# kamstrup-wifi.net
KiCad netlist of a schematic drawn in EAGLE
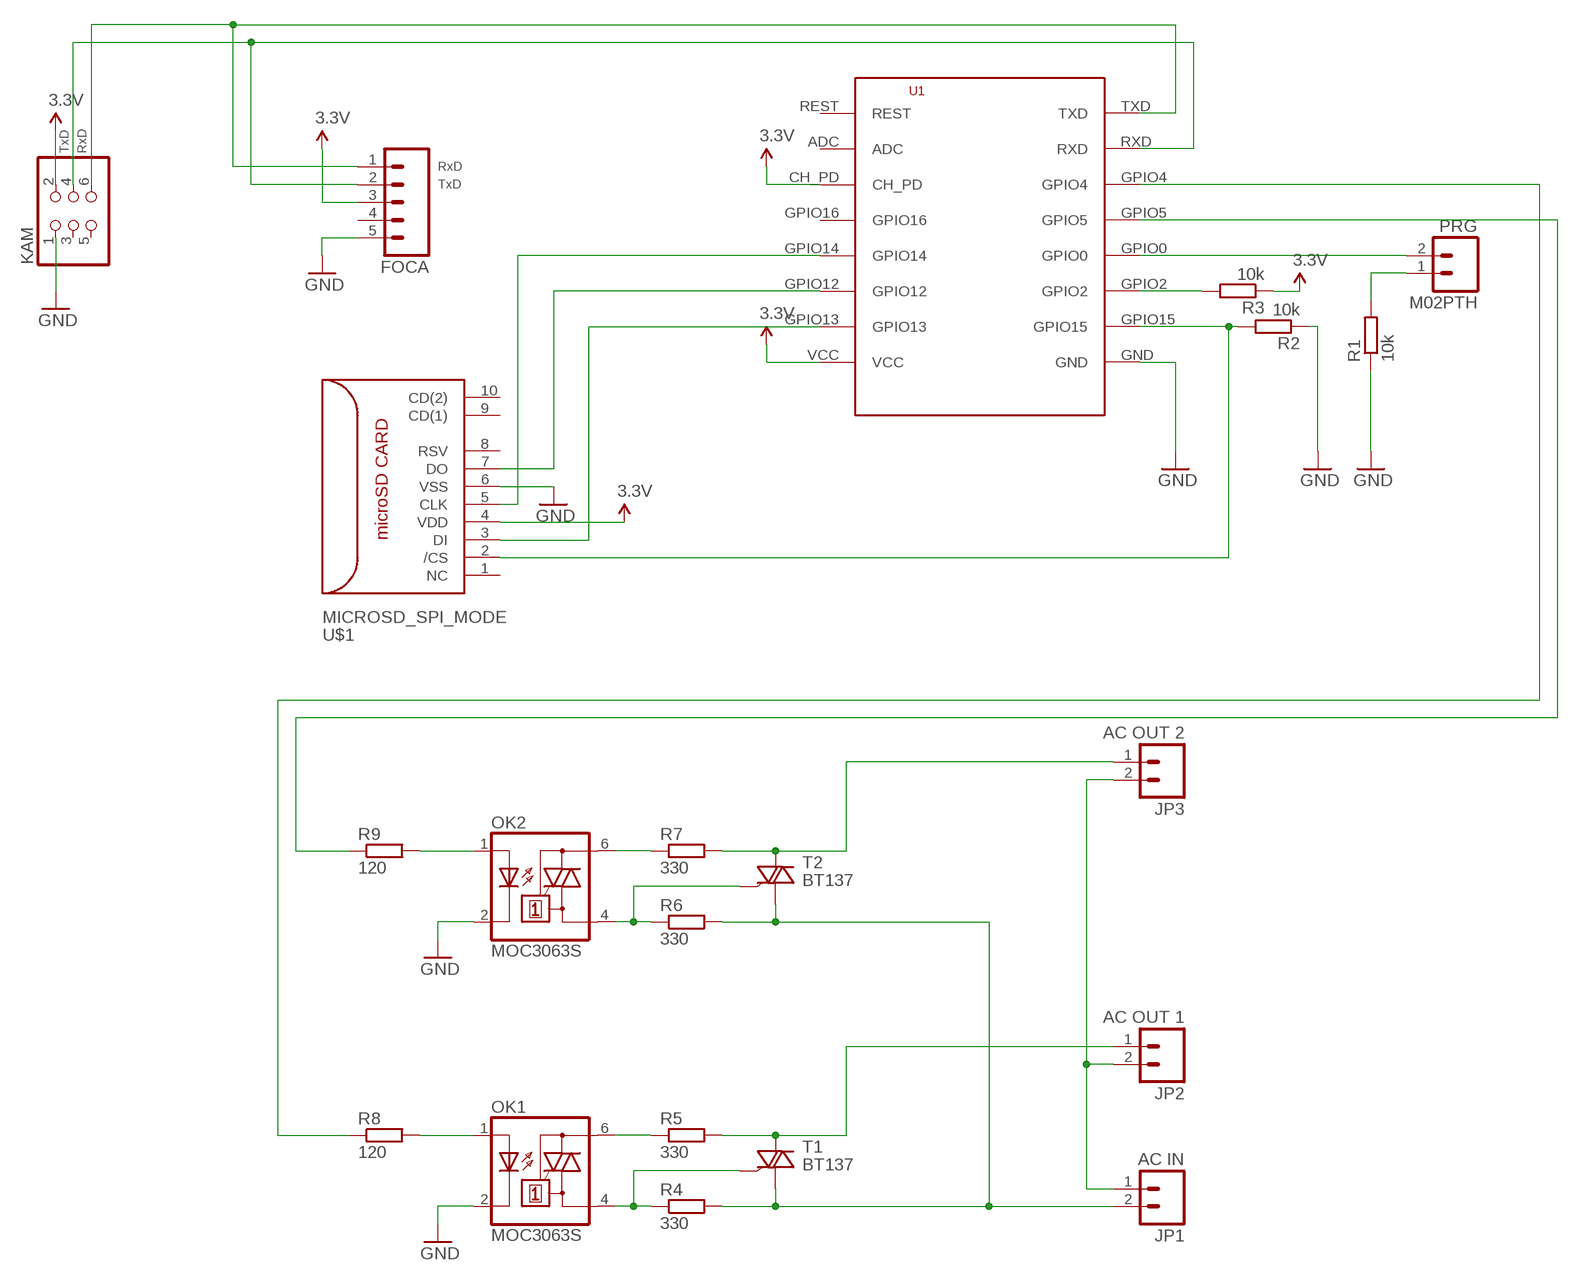
[diagram p0: schematic, sheet 1]

(export (version "E")
  (design (tool "Eeschema 10.0.6"))
  (components
    (comp (ref "FOCA")
      (value "M05PTH")
      (footprint "eagle-import:1X05")
      (libsource (lib "eagle-import") (part "M05PTH"))
    )
    (comp (ref "JP1")
      (value "AC IN")
      (footprint "eagle-import:SCREWTERMINAL-5MM-2")
      (libsource (lib "eagle-import") (part "TE Terminal Block 45 degrees_M025MM"))
    )
    (comp (ref "JP2")
      (value "AC OUT 1")
      (footprint "eagle-import:SCREWTERMINAL-5MM-2")
      (libsource (lib "eagle-import") (part "TE Terminal Block 45 degrees_M025MM"))
    )
    (comp (ref "JP3")
      (value "AC OUT 2")
      (footprint "eagle-import:SCREWTERMINAL-5MM-2")
      (libsource (lib "eagle-import") (part "TE Terminal Block 45 degrees_M025MM"))
    )
    (comp (ref "KAM")
      (value "PINHD-2X3")
      (footprint "eagle-import:2X03")
      (libsource (lib "eagle-import") (part "PINHD-2X3"))
    )
    (comp (ref "OK1")
      (value "MOC3063S")
      (footprint "eagle-import:DIL6-SMD")
      (fields (field (name "MF") "FAIRCHILD SEMICONDUCTOR") (field (name "MPN") "MOC3043SM"))
      (libsource (lib "eagle-import") (part "MOC30S43"))
    )
    (comp (ref "OK2")
      (value "MOC3063S")
      (footprint "eagle-import:DIL6-SMD")
      (fields (field (name "MF") "FAIRCHILD SEMICONDUCTOR") (field (name "MPN") "MOC3043SM"))
      (libsource (lib "eagle-import") (part "MOC30S43"))
    )
    (comp (ref "PRG")
      (value "M02PTH")
      (footprint "eagle-import:1X02")
      (libsource (lib "eagle-import") (part "M02PTH"))
    )
    (comp (ref "R1")
      (value "10k")
      (footprint "eagle-import:R0805")
      (libsource (lib "eagle-import") (part "R-EU_R0805"))
    )
    (comp (ref "R2")
      (value "10k")
      (footprint "eagle-import:R0805")
      (libsource (lib "eagle-import") (part "R-EU_R0805"))
    )
    (comp (ref "R3")
      (value "10k")
      (footprint "eagle-import:R0805")
      (libsource (lib "eagle-import") (part "R-EU_R0805"))
    )
    (comp (ref "R4")
      (value "330")
      (footprint "eagle-import:R0805")
      (libsource (lib "eagle-import") (part "R-EU_R0805"))
    )
    (comp (ref "R5")
      (value "330")
      (footprint "eagle-import:R0805")
      (libsource (lib "eagle-import") (part "R-EU_R0805"))
    )
    (comp (ref "R6")
      (value "330")
      (footprint "eagle-import:R0805")
      (libsource (lib "eagle-import") (part "R-EU_R0805"))
    )
    (comp (ref "R7")
      (value "330")
      (footprint "eagle-import:R0805")
      (libsource (lib "eagle-import") (part "R-EU_R0805"))
    )
    (comp (ref "R8")
      (value "120")
      (footprint "eagle-import:R0805")
      (libsource (lib "eagle-import") (part "R-EU_R0805"))
    )
    (comp (ref "R9")
      (value "120")
      (footprint "eagle-import:R0805")
      (libsource (lib "eagle-import") (part "R-EU_R0805"))
    )
    (comp (ref "T1")
      (value "BT137")
      (footprint "eagle-import:SOT428")
      (libsource (lib "eagle-import") (part "BT137"))
    )
    (comp (ref "T2")
      (value "BT137")
      (footprint "eagle-import:SOT428")
      (libsource (lib "eagle-import") (part "BT137"))
    )
    (comp (ref "U$1")
      (value "MICROSD_SPI_MODE")
      (footprint "eagle-import:MICRO_SD_CONNECTOR")
      (libsource (lib "eagle-import") (part "MICROSD_SPI_MODE"))
    )
    (comp (ref "U1")
      (value "ESP8266-07")
      (footprint "eagle-import:ESP-07")
      (libsource (lib "eagle-import") (part "ESP8266-07"))
    )
  )
  (nets
    (net (code "1") (name "3.3V") (class "Default")
      (node (ref "FOCA") (pin "3") (pinfunction "3_3") (pintype "passive"))
      (node (ref "KAM") (pin "2") (pinfunction "2_2") (pintype "passive"))
      (node (ref "R3") (pin "1") (pinfunction "1_1") (pintype "passive"))
      (node (ref "U$1") (pin "4") (pinfunction "VDD_4") (pintype "bidirectional"))
      (node (ref "U1") (pin "CH_PD") (pinfunction "CH_PD_CH_PD") (pintype "bidirectional"))
      (node (ref "U1") (pin "VCC") (pinfunction "VCC_VCC") (pintype "bidirectional"))
    )
    (net (code "2") (name "GND") (class "Default")
      (node (ref "FOCA") (pin "5") (pinfunction "5_5") (pintype "passive"))
      (node (ref "KAM") (pin "1") (pinfunction "1_1") (pintype "passive"))
      (node (ref "OK1") (pin "2") (pinfunction "C_2") (pintype "passive"))
      (node (ref "OK2") (pin "2") (pinfunction "C_2") (pintype "passive"))
      (node (ref "R1") (pin "1") (pinfunction "1_1") (pintype "passive"))
      (node (ref "R2") (pin "1") (pinfunction "1_1") (pintype "passive"))
      (node (ref "U$1") (pin "6") (pinfunction "VSS_6") (pintype "bidirectional"))
      (node (ref "U1") (pin "GND") (pinfunction "GND_GND") (pintype "power_in"))
    )
    (net (code "3") (name "Net-(FOCA-Pad1)") (class "Default")
      (node (ref "FOCA") (pin "1") (pinfunction "1_1") (pintype "passive"))
      (node (ref "KAM") (pin "6") (pinfunction "6_6") (pintype "passive"))
      (node (ref "U1") (pin "TXD") (pinfunction "TXD_TXD") (pintype "bidirectional"))
    )
    (net (code "4") (name "Net-(FOCA-Pad2)") (class "Default")
      (node (ref "FOCA") (pin "2") (pinfunction "2_2") (pintype "passive"))
      (node (ref "KAM") (pin "4") (pinfunction "4_4") (pintype "passive"))
      (node (ref "U1") (pin "RXD") (pinfunction "RXD_RXD") (pintype "bidirectional"))
    )
    (net (code "5") (name "Net-(JP1-Pad1)") (class "Default")
      (node (ref "JP1") (pin "1") (pinfunction "1_1") (pintype "passive"))
      (node (ref "JP2") (pin "2") (pinfunction "2_2") (pintype "passive"))
      (node (ref "JP3") (pin "2") (pinfunction "2_2") (pintype "passive"))
    )
    (net (code "6") (name "Net-(OK1-A)") (class "Default")
      (node (ref "OK1") (pin "1") (pinfunction "A_1") (pintype "passive"))
      (node (ref "R8") (pin "2") (pinfunction "2_2") (pintype "passive"))
    )
    (net (code "7") (name "Net-(OK1-A1)") (class "Default")
      (node (ref "OK1") (pin "4") (pinfunction "A1_4") (pintype "passive"))
      (node (ref "R4") (pin "1") (pinfunction "1_1") (pintype "passive"))
      (node (ref "T1") (pin "3") (pinfunction "G_3") (pintype "passive"))
    )
    (net (code "8") (name "Net-(OK1-A2)") (class "Default")
      (node (ref "OK1") (pin "6") (pinfunction "A2_6") (pintype "passive"))
      (node (ref "R5") (pin "1") (pinfunction "1_1") (pintype "passive"))
    )
    (net (code "9") (name "Net-(OK2-A)") (class "Default")
      (node (ref "OK2") (pin "1") (pinfunction "A_1") (pintype "passive"))
      (node (ref "R9") (pin "2") (pinfunction "2_2") (pintype "passive"))
    )
    (net (code "10") (name "Net-(OK2-A1)") (class "Default")
      (node (ref "OK2") (pin "4") (pinfunction "A1_4") (pintype "passive"))
      (node (ref "R6") (pin "1") (pinfunction "1_1") (pintype "passive"))
      (node (ref "T2") (pin "3") (pinfunction "G_3") (pintype "passive"))
    )
    (net (code "11") (name "Net-(OK2-A2)") (class "Default")
      (node (ref "OK2") (pin "6") (pinfunction "A2_6") (pintype "passive"))
      (node (ref "R7") (pin "1") (pinfunction "1_1") (pintype "passive"))
    )
    (net (code "12") (name "Net-(PRG-Pad1)") (class "Default")
      (node (ref "PRG") (pin "1") (pinfunction "1_1") (pintype "passive"))
      (node (ref "R1") (pin "2") (pinfunction "2_2") (pintype "passive"))
    )
    (net (code "13") (name "Net-(PRG-Pad2)") (class "Default")
      (node (ref "PRG") (pin "2") (pinfunction "2_2") (pintype "passive"))
      (node (ref "U1") (pin "GPIO0") (pinfunction "GPIO0_GPIO0") (pintype "bidirectional"))
    )
    (net (code "14") (name "Net-(R3-Pad2)") (class "Default")
      (node (ref "R3") (pin "2") (pinfunction "2_2") (pintype "passive"))
      (node (ref "U1") (pin "GPIO2") (pinfunction "GPIO2_GPIO2") (pintype "bidirectional"))
    )
    (net (code "15") (name "Net-(R8-Pad1)") (class "Default")
      (node (ref "R8") (pin "1") (pinfunction "1_1") (pintype "passive"))
      (node (ref "U1") (pin "GPIO4") (pinfunction "GPIO4_GPIO4") (pintype "bidirectional"))
    )
    (net (code "16") (name "Net-(R9-Pad1)") (class "Default")
      (node (ref "R9") (pin "1") (pinfunction "1_1") (pintype "passive"))
      (node (ref "U1") (pin "GPIO5") (pinfunction "GPIO5_GPIO5") (pintype "bidirectional"))
    )
    (net (code "17") (name "Net-(T1-A1)") (class "Default")
      (node (ref "JP1") (pin "2") (pinfunction "2_2") (pintype "passive"))
      (node (ref "R4") (pin "2") (pinfunction "2_2") (pintype "passive"))
      (node (ref "R6") (pin "2") (pinfunction "2_2") (pintype "passive"))
      (node (ref "T1") (pin "1") (pinfunction "A1_1") (pintype "passive"))
      (node (ref "T2") (pin "1") (pinfunction "A1_1") (pintype "passive"))
    )
    (net (code "18") (name "Net-(T1-A2)") (class "Default")
      (node (ref "JP2") (pin "1") (pinfunction "1_1") (pintype "passive"))
      (node (ref "R5") (pin "2") (pinfunction "2_2") (pintype "passive"))
      (node (ref "T1") (pin "4") (pinfunction "A2_4") (pintype "passive"))
    )
    (net (code "19") (name "Net-(T2-A2)") (class "Default")
      (node (ref "JP3") (pin "1") (pinfunction "1_1") (pintype "passive"))
      (node (ref "R7") (pin "2") (pinfunction "2_2") (pintype "passive"))
      (node (ref "T2") (pin "4") (pinfunction "A2_4") (pintype "passive"))
    )
    (net (code "20") (name "Net-(U$1-CLK)") (class "Default")
      (node (ref "U$1") (pin "5") (pinfunction "CLK_5") (pintype "bidirectional"))
      (node (ref "U1") (pin "GPIO14") (pinfunction "GPIO14_GPIO14") (pintype "bidirectional"))
    )
    (net (code "21") (name "Net-(U$1-DI)") (class "Default")
      (node (ref "U$1") (pin "3") (pinfunction "DI_3") (pintype "bidirectional"))
      (node (ref "U1") (pin "GPIO13") (pinfunction "GPIO13_GPIO13") (pintype "bidirectional"))
    )
    (net (code "22") (name "Net-(U$1-DO)") (class "Default")
      (node (ref "U$1") (pin "7") (pinfunction "DO_7") (pintype "bidirectional"))
      (node (ref "U1") (pin "GPIO12") (pinfunction "GPIO12_GPIO12") (pintype "bidirectional"))
    )
    (net (code "23") (name "Net-(U$1-{slash}CS)") (class "Default")
      (node (ref "R2") (pin "2") (pinfunction "2_2") (pintype "passive"))
      (node (ref "U$1") (pin "2") (pinfunction "/CS_2") (pintype "bidirectional"))
      (node (ref "U1") (pin "GPIO15") (pinfunction "GPIO15_GPIO15") (pintype "bidirectional"))
    )
    (net (code "24") (name "unconnected-(FOCA-Pad4)") (class "Default")
      (node (ref "FOCA") (pin "4") (pinfunction "4_4") (pintype "passive"))
    )
    (net (code "25") (name "unconnected-(KAM-Pad3)") (class "Default")
      (node (ref "KAM") (pin "3") (pinfunction "3_3") (pintype "passive"))
    )
    (net (code "26") (name "unconnected-(KAM-Pad5)") (class "Default")
      (node (ref "KAM") (pin "5") (pinfunction "5_5") (pintype "passive"))
    )
    (net (code "27") (name "unconnected-(U$1-CD(1)-Pad9)") (class "Default")
      (node (ref "U$1") (pin "9") (pinfunction "CD(1)_9") (pintype "bidirectional"))
    )
    (net (code "28") (name "unconnected-(U$1-CD(2)-Pad10)") (class "Default")
      (node (ref "U$1") (pin "10") (pinfunction "CD(2)_10") (pintype "bidirectional"))
    )
    (net (code "29") (name "unconnected-(U$1-NC-Pad1)") (class "Default")
      (node (ref "U$1") (pin "1") (pinfunction "NC_1") (pintype "bidirectional"))
    )
    (net (code "30") (name "unconnected-(U$1-RSV-Pad8)") (class "Default")
      (node (ref "U$1") (pin "8") (pinfunction "RSV_8") (pintype "bidirectional"))
    )
    (net (code "31") (name "unconnected-(U1-PadADC)") (class "Default")
      (node (ref "U1") (pin "ADC") (pinfunction "ADC_ADC") (pintype "bidirectional"))
    )
    (net (code "32") (name "unconnected-(U1-PadGPIO16)") (class "Default")
      (node (ref "U1") (pin "GPIO16") (pinfunction "GPIO16_GPIO16") (pintype "bidirectional"))
    )
    (net (code "33") (name "unconnected-(U1-PadREST)") (class "Default")
      (node (ref "U1") (pin "REST") (pinfunction "REST_REST") (pintype "bidirectional"))
    )
  )
)
